# 03_-_WiFi.net
KiCad netlist of a schematic drawn in Altium Designer
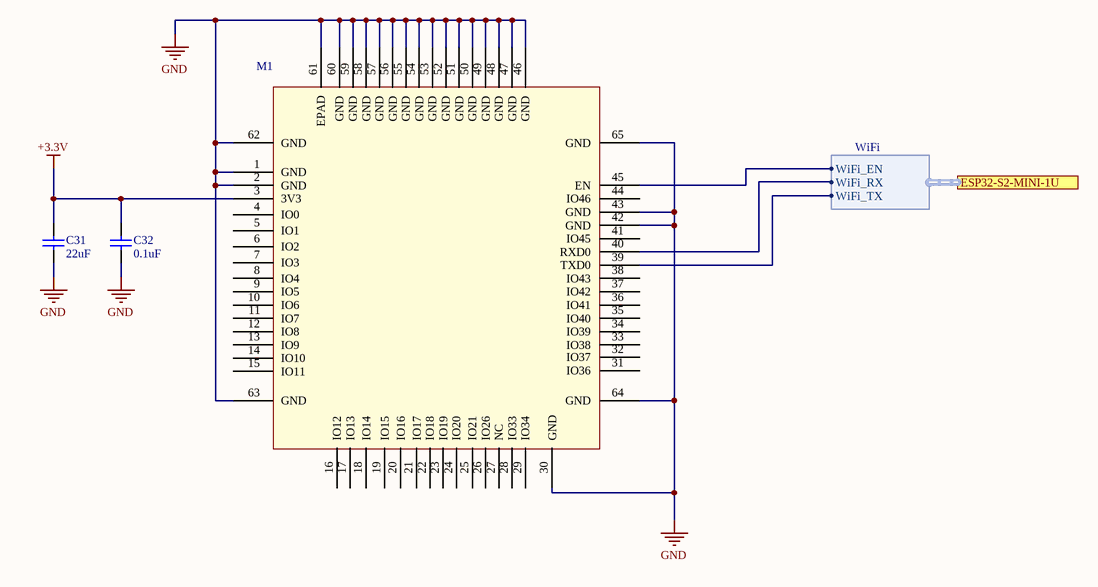
[diagram p0: [03] - WiFi.SchDoc]

(export (version "E")
  (design (tool "Eeschema 10.0.6"))
  (components
    (comp (ref "C31")
      (value "22uF")
      (footprint "SMD(0805)")
      (description "Capacitor")
      (fields (field (name "Comment") "Cap"))
      (libsource (lib "MyLib") (part "Cap"))
    )
    (comp (ref "C32")
      (value "0.1uF")
      (footprint "SMD(0805)")
      (description "Capacitor")
      (fields (field (name "Comment") "Cap"))
      (libsource (lib "MyLib") (part "Cap"))
    )
    (comp (ref "M1")
      (value "ESP32-S2-MINI-1U _Module")
      (description "Esp-32-S2-MINI-1U")
      (libsource (lib "ESP32-S2-MINI-1U") (part "ESP32-S2-MINI-1U _Module"))
    )
  )
  (nets
    (net (code "2") (name "+3.3V") (class "Default")
      (node (ref "C31") (pin "2") (pinfunction "2_2") (pintype "passive"))
      (node (ref "C32") (pin "2") (pinfunction "2_2") (pintype "passive"))
      (node (ref "M1") (pin "3") (pinfunction "3V3_3") (pintype "power_in"))
    )
    (net (code "3") (name "/WiFi_EN") (class "Default")
      (node (ref "M1") (pin "45") (pinfunction "EN_45") (pintype "power_in"))
    )
    (net (code "4") (name "/WiFi_RX") (class "Default")
      (node (ref "M1") (pin "40") (pinfunction "RXD0_40") (pintype "passive"))
    )
    (net (code "5") (name "/WiFi_TX") (class "Default")
      (node (ref "M1") (pin "39") (pinfunction "TXD0_39") (pintype "passive"))
    )
    (net (code "7") (name "GND") (class "Default")
      (node (ref "C31") (pin "1") (pinfunction "1_1") (pintype "passive"))
      (node (ref "C32") (pin "1") (pinfunction "1_1") (pintype "passive"))
      (node (ref "M1") (pin "1") (pinfunction "GND_1") (pintype "power_in"))
      (node (ref "M1") (pin "2") (pinfunction "GND_2") (pintype "power_in"))
      (node (ref "M1") (pin "30") (pinfunction "GND_30") (pintype "power_in"))
      (node (ref "M1") (pin "42") (pinfunction "GND_42") (pintype "passive"))
      (node (ref "M1") (pin "43") (pinfunction "GND_43") (pintype "passive"))
      (node (ref "M1") (pin "46") (pinfunction "GND_46") (pintype "power_in"))
      (node (ref "M1") (pin "47") (pinfunction "GND_47") (pintype "power_in"))
      (node (ref "M1") (pin "48") (pinfunction "GND_48") (pintype "power_in"))
      (node (ref "M1") (pin "49") (pinfunction "GND_49") (pintype "power_in"))
      (node (ref "M1") (pin "50") (pinfunction "GND_50") (pintype "power_in"))
      (node (ref "M1") (pin "51") (pinfunction "GND_51") (pintype "power_in"))
      (node (ref "M1") (pin "52") (pinfunction "GND_52") (pintype "power_in"))
      (node (ref "M1") (pin "53") (pinfunction "GND_53") (pintype "power_in"))
      (node (ref "M1") (pin "54") (pinfunction "GND_54") (pintype "power_in"))
      (node (ref "M1") (pin "55") (pinfunction "GND_55") (pintype "power_in"))
      (node (ref "M1") (pin "56") (pinfunction "GND_56") (pintype "power_in"))
      (node (ref "M1") (pin "57") (pinfunction "GND_57") (pintype "power_in"))
      (node (ref "M1") (pin "58") (pinfunction "GND_58") (pintype "power_in"))
      (node (ref "M1") (pin "59") (pinfunction "GND_59") (pintype "power_in"))
      (node (ref "M1") (pin "60") (pinfunction "GND_60") (pintype "power_in"))
      (node (ref "M1") (pin "61") (pinfunction "EPAD_61") (pintype "power_in"))
      (node (ref "M1") (pin "62") (pinfunction "GND_62") (pintype "power_in"))
      (node (ref "M1") (pin "63") (pinfunction "GND_63") (pintype "passive"))
      (node (ref "M1") (pin "64") (pinfunction "GND_64") (pintype "passive"))
      (node (ref "M1") (pin "65") (pinfunction "GND_65") (pintype "power_in"))
    )
    (net (code "8") (name "unconnected-(M1-IO0-Pad4)") (class "Default")
      (node (ref "M1") (pin "4") (pinfunction "IO0_4") (pintype "passive"))
    )
    (net (code "9") (name "unconnected-(M1-IO1-Pad5)") (class "Default")
      (node (ref "M1") (pin "5") (pinfunction "IO1_5") (pintype "passive"))
    )
    (net (code "10") (name "unconnected-(M1-IO2-Pad6)") (class "Default")
      (node (ref "M1") (pin "6") (pinfunction "IO2_6") (pintype "passive"))
    )
    (net (code "11") (name "unconnected-(M1-IO3-Pad7)") (class "Default")
      (node (ref "M1") (pin "7") (pinfunction "IO3_7") (pintype "passive"))
    )
    (net (code "12") (name "unconnected-(M1-IO4-Pad8)") (class "Default")
      (node (ref "M1") (pin "8") (pinfunction "IO4_8") (pintype "passive"))
    )
    (net (code "13") (name "unconnected-(M1-IO5-Pad9)") (class "Default")
      (node (ref "M1") (pin "9") (pinfunction "IO5_9") (pintype "passive"))
    )
    (net (code "14") (name "unconnected-(M1-IO6-Pad10)") (class "Default")
      (node (ref "M1") (pin "10") (pinfunction "IO6_10") (pintype "passive"))
    )
    (net (code "15") (name "unconnected-(M1-IO7-Pad11)") (class "Default")
      (node (ref "M1") (pin "11") (pinfunction "IO7_11") (pintype "passive"))
    )
    (net (code "16") (name "unconnected-(M1-IO8-Pad12)") (class "Default")
      (node (ref "M1") (pin "12") (pinfunction "IO8_12") (pintype "passive"))
    )
    (net (code "17") (name "unconnected-(M1-IO9-Pad13)") (class "Default")
      (node (ref "M1") (pin "13") (pinfunction "IO9_13") (pintype "passive"))
    )
    (net (code "18") (name "unconnected-(M1-IO10-Pad14)") (class "Default")
      (node (ref "M1") (pin "14") (pinfunction "IO10_14") (pintype "passive"))
    )
    (net (code "19") (name "unconnected-(M1-IO11-Pad15)") (class "Default")
      (node (ref "M1") (pin "15") (pinfunction "IO11_15") (pintype "passive"))
    )
    (net (code "20") (name "unconnected-(M1-IO12-Pad16)") (class "Default")
      (node (ref "M1") (pin "16") (pinfunction "IO12_16") (pintype "passive"))
    )
    (net (code "21") (name "unconnected-(M1-IO13-Pad17)") (class "Default")
      (node (ref "M1") (pin "17") (pinfunction "IO13_17") (pintype "passive"))
    )
    (net (code "22") (name "unconnected-(M1-IO14-Pad18)") (class "Default")
      (node (ref "M1") (pin "18") (pinfunction "IO14_18") (pintype "passive"))
    )
    (net (code "23") (name "unconnected-(M1-IO15-Pad19)") (class "Default")
      (node (ref "M1") (pin "19") (pinfunction "IO15_19") (pintype "passive"))
    )
    (net (code "24") (name "unconnected-(M1-IO16-Pad20)") (class "Default")
      (node (ref "M1") (pin "20") (pinfunction "IO16_20") (pintype "passive"))
    )
    (net (code "25") (name "unconnected-(M1-IO17-Pad21)") (class "Default")
      (node (ref "M1") (pin "21") (pinfunction "IO17_21") (pintype "passive"))
    )
    (net (code "26") (name "unconnected-(M1-IO18-Pad22)") (class "Default")
      (node (ref "M1") (pin "22") (pinfunction "IO18_22") (pintype "passive"))
    )
    (net (code "27") (name "unconnected-(M1-IO19-Pad23)") (class "Default")
      (node (ref "M1") (pin "23") (pinfunction "IO19_23") (pintype "passive"))
    )
    (net (code "28") (name "unconnected-(M1-IO20-Pad24)") (class "Default")
      (node (ref "M1") (pin "24") (pinfunction "IO20_24") (pintype "passive"))
    )
    (net (code "29") (name "unconnected-(M1-IO21-Pad25)") (class "Default")
      (node (ref "M1") (pin "25") (pinfunction "IO21_25") (pintype "passive"))
    )
    (net (code "30") (name "unconnected-(M1-IO26-Pad26)") (class "Default")
      (node (ref "M1") (pin "26") (pinfunction "IO26_26") (pintype "passive"))
    )
    (net (code "31") (name "unconnected-(M1-IO33-Pad28)") (class "Default")
      (node (ref "M1") (pin "28") (pinfunction "IO33_28") (pintype "passive"))
    )
    (net (code "32") (name "unconnected-(M1-IO34-Pad29)") (class "Default")
      (node (ref "M1") (pin "29") (pinfunction "IO34_29") (pintype "passive"))
    )
    (net (code "33") (name "unconnected-(M1-IO36-Pad31)") (class "Default")
      (node (ref "M1") (pin "31") (pinfunction "IO36_31") (pintype "passive"))
    )
    (net (code "34") (name "unconnected-(M1-IO37-Pad32)") (class "Default")
      (node (ref "M1") (pin "32") (pinfunction "IO37_32") (pintype "passive"))
    )
    (net (code "35") (name "unconnected-(M1-IO38-Pad33)") (class "Default")
      (node (ref "M1") (pin "33") (pinfunction "IO38_33") (pintype "passive"))
    )
    (net (code "36") (name "unconnected-(M1-IO39-Pad34)") (class "Default")
      (node (ref "M1") (pin "34") (pinfunction "IO39_34") (pintype "passive"))
    )
    (net (code "37") (name "unconnected-(M1-IO40-Pad35)") (class "Default")
      (node (ref "M1") (pin "35") (pinfunction "IO40_35") (pintype "passive"))
    )
    (net (code "38") (name "unconnected-(M1-IO41-Pad36)") (class "Default")
      (node (ref "M1") (pin "36") (pinfunction "IO41_36") (pintype "passive"))
    )
    (net (code "39") (name "unconnected-(M1-IO42-Pad37)") (class "Default")
      (node (ref "M1") (pin "37") (pinfunction "IO42_37") (pintype "passive"))
    )
    (net (code "40") (name "unconnected-(M1-IO43-Pad38)") (class "Default")
      (node (ref "M1") (pin "38") (pinfunction "IO43_38") (pintype "passive"))
    )
    (net (code "41") (name "unconnected-(M1-IO45-Pad41)") (class "Default")
      (node (ref "M1") (pin "41") (pinfunction "IO45_41") (pintype "passive"))
    )
    (net (code "42") (name "unconnected-(M1-IO46-Pad44)") (class "Default")
      (node (ref "M1") (pin "44") (pinfunction "IO46_44") (pintype "passive"))
    )
    (net (code "43") (name "unconnected-(M1-NC-Pad27)") (class "Default")
      (node (ref "M1") (pin "27") (pinfunction "NC_27") (pintype "passive"))
    )
  )
)
